# LCD.net
KiCad netlist of a schematic drawn in Altium Designer
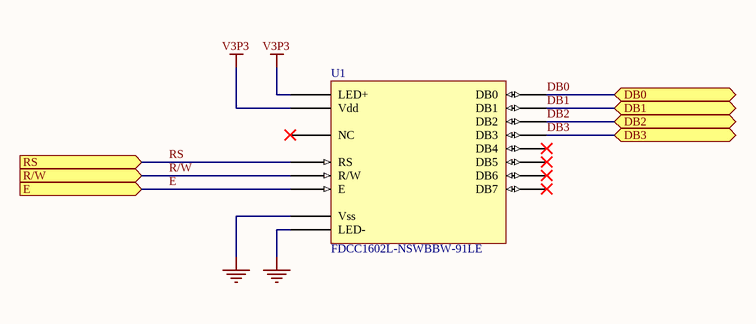
[diagram p0: LCD.SchDoc]

(export (version "E")
  (design (tool "Eeschema 10.0.6"))
  (components
    (comp (ref "U1")
      (value "FDCC1602L-NSWBBW-91LE")
      (footprint "LCD (Only header)")
      (libsource (lib "Card_reader") (part "FDCC1602L-NSWBBW-91LE"))
    )
  )
  (nets
    (net (code "1") (name "/DB0") (class "Default")
      (node (ref "U1") (pin "7") (pinfunction "DB0_7") (pintype "bidirectional"))
    )
    (net (code "2") (name "/DB1") (class "Default")
      (node (ref "U1") (pin "8") (pinfunction "DB1_8") (pintype "bidirectional"))
    )
    (net (code "3") (name "/DB2") (class "Default")
      (node (ref "U1") (pin "9") (pinfunction "DB2_9") (pintype "bidirectional"))
    )
    (net (code "4") (name "/DB3") (class "Default")
      (node (ref "U1") (pin "10") (pinfunction "DB3_10") (pintype "bidirectional"))
    )
    (net (code "5") (name "/E") (class "Default")
      (node (ref "U1") (pin "6") (pinfunction "E_6") (pintype "input"))
    )
    (net (code "6") (name "/RS") (class "Default")
      (node (ref "U1") (pin "4") (pinfunction "RS_4") (pintype "input"))
    )
    (net (code "7") (name "/R{slash}W") (class "Default")
      (node (ref "U1") (pin "5") (pinfunction "R/W_5") (pintype "input"))
    )
    (net (code "8") (name "GND") (class "Default")
      (node (ref "U1") (pin "1") (pinfunction "Vss_1") (pintype "power_in"))
      (node (ref "U1") (pin "16") (pinfunction "LED-_16") (pintype "power_in"))
    )
    (net (code "9") (name "V3P3") (class "Default")
      (node (ref "U1") (pin "15") (pinfunction "LED+_15") (pintype "power_in"))
      (node (ref "U1") (pin "2") (pinfunction "Vdd_2") (pintype "power_in"))
    )
    (net (code "10") (name "unconnected-(U1-DB4-Pad11)") (class "Default")
      (node (ref "U1") (pin "11") (pinfunction "DB4_11") (pintype "bidirectional+no_connect"))
    )
    (net (code "11") (name "unconnected-(U1-DB5-Pad12)") (class "Default")
      (node (ref "U1") (pin "12") (pinfunction "DB5_12") (pintype "bidirectional+no_connect"))
    )
    (net (code "12") (name "unconnected-(U1-DB6-Pad13)") (class "Default")
      (node (ref "U1") (pin "13") (pinfunction "DB6_13") (pintype "bidirectional+no_connect"))
    )
    (net (code "13") (name "unconnected-(U1-DB7-Pad14)") (class "Default")
      (node (ref "U1") (pin "14") (pinfunction "DB7_14") (pintype "bidirectional+no_connect"))
    )
    (net (code "14") (name "unconnected-(U1-NC-Pad3)") (class "Default")
      (node (ref "U1") (pin "3") (pinfunction "NC_3") (pintype "passive+no_connect"))
    )
  )
)
